# RFM-XXXXS_Module.net
KiCad netlist of a schematic drawn in EAGLE
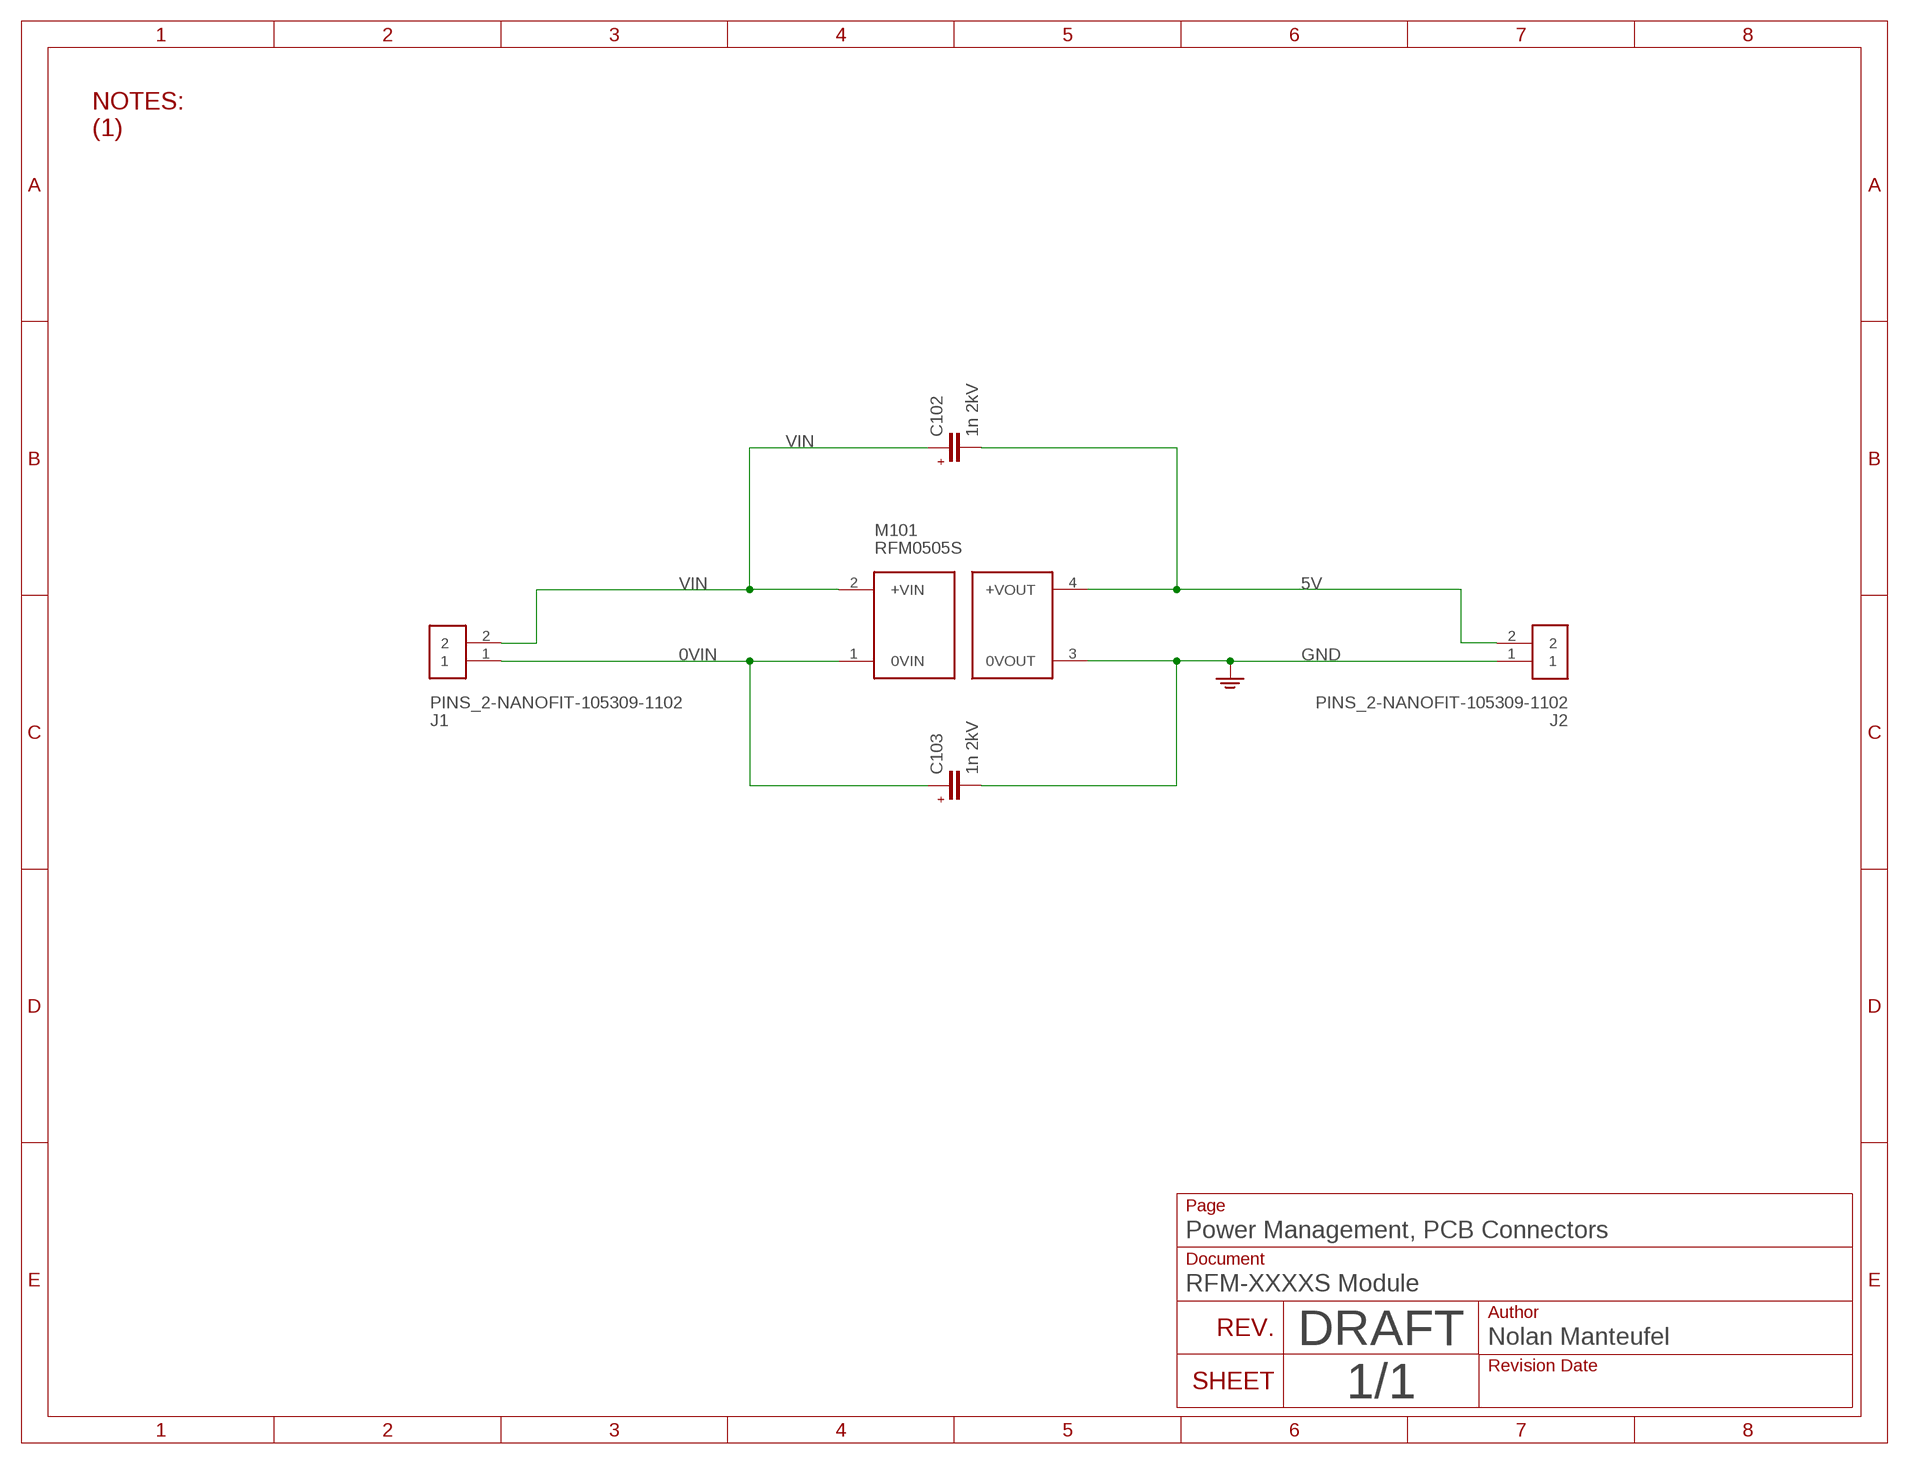
[diagram p0: schematic, sheet 1]

(export (version "E")
  (design (tool "Eeschema 10.0.6"))
  (components
    (comp (ref "C102")
      (value "1n 2kV")
      (footprint "eagle-import:C050-024X044")
      (libsource (lib "eagle-import") (part "COVAL"))
    )
    (comp (ref "C103")
      (value "1n 2kV")
      (footprint "eagle-import:C050-024X044")
      (libsource (lib "eagle-import") (part "COVAL"))
    )
    (comp (ref "J1")
      (value "PINS_2-NANOFIT-105309-1102")
      (footprint "eagle-import:PINS_2-NANOFIT")
      (libsource (lib "eagle-import") (part "PINS_2-NANOFIT-105309-1102"))
    )
    (comp (ref "J2")
      (value "PINS_2-NANOFIT-105309-1102")
      (footprint "eagle-import:PINS_2-NANOFIT")
      (libsource (lib "eagle-import") (part "PINS_2-NANOFIT-105309-1102"))
    )
    (comp (ref "M101")
      (value "RFM0505S")
      (footprint "eagle-import:RFM-XXXXS")
      (libsource (lib "eagle-import") (part "DCDC_ISOLATORRFM-XXXXS"))
    )
  )
  (nets
    (net (code "1") (name "/0VIN") (class "Default")
      (node (ref "C103") (pin "2") (pinfunction "+_2") (pintype "passive"))
      (node (ref "J1") (pin "1") (pinfunction "1_1") (pintype "bidirectional"))
      (node (ref "M101") (pin "1") (pinfunction "0VIN_1") (pintype "bidirectional"))
    )
    (net (code "2") (name "/5V") (class "Default")
      (node (ref "C102") (pin "1") (pinfunction "-_1") (pintype "passive"))
      (node (ref "J2") (pin "2") (pinfunction "2_2") (pintype "bidirectional"))
      (node (ref "M101") (pin "4") (pinfunction "+VOUT_4") (pintype "bidirectional"))
    )
    (net (code "3") (name "/VIN") (class "Default")
      (node (ref "C102") (pin "2") (pinfunction "+_2") (pintype "passive"))
      (node (ref "J1") (pin "2") (pinfunction "2_2") (pintype "bidirectional"))
      (node (ref "M101") (pin "2") (pinfunction "+VIN_2") (pintype "bidirectional"))
    )
    (net (code "4") (name "GND") (class "Default")
      (node (ref "C103") (pin "1") (pinfunction "-_1") (pintype "passive"))
      (node (ref "J2") (pin "1") (pinfunction "1_1") (pintype "bidirectional"))
      (node (ref "M101") (pin "3") (pinfunction "0VOUT_3") (pintype "bidirectional"))
    )
  )
)
